# bldc_driver.net
KiCad netlist of a schematic drawn in EAGLE
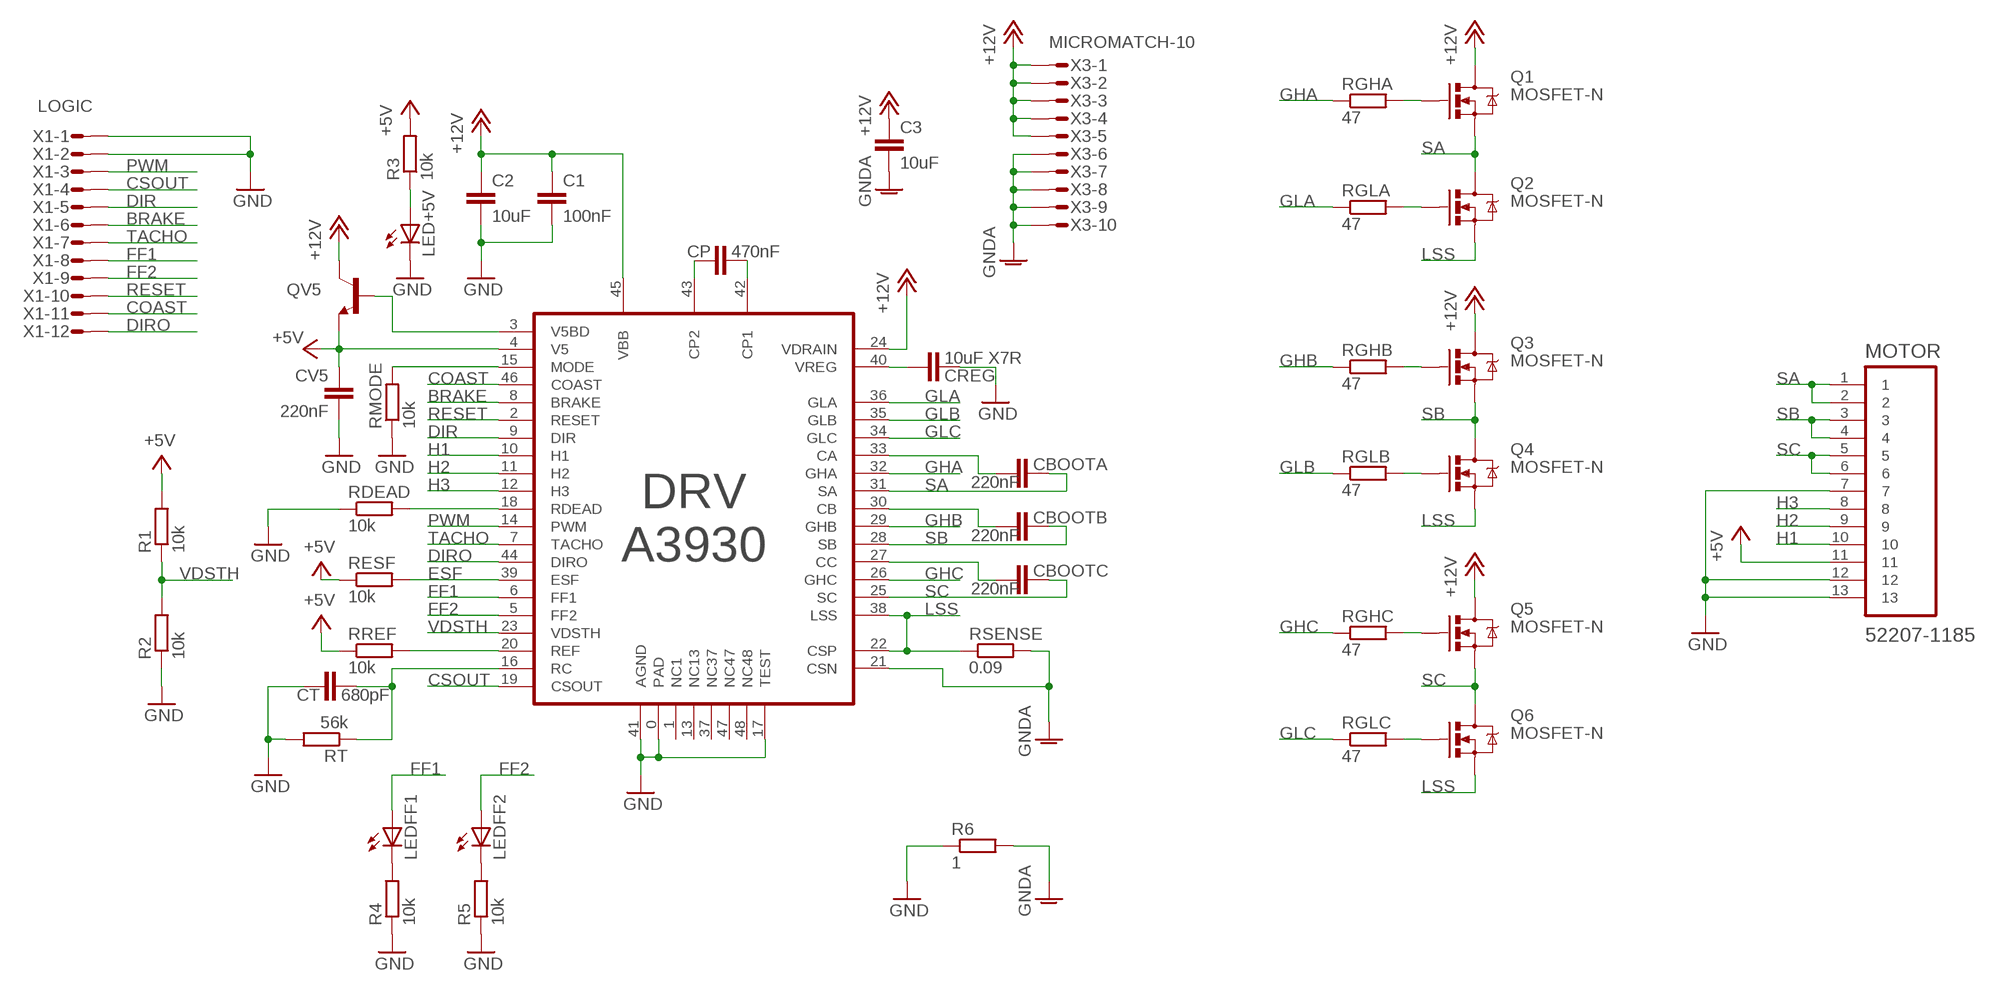
[diagram p0: schematic, sheet 1]

(export (version "E")
  (design (tool "Eeschema 10.0.6"))
  (components
    (comp (ref "C1")
      (value "100nF")
      (footprint "eagle-import:C0603")
      (libsource (lib "eagle-import") (part "C-EUC0603"))
    )
    (comp (ref "C2")
      (value "10uF")
      (footprint "eagle-import:C1206K")
      (libsource (lib "eagle-import") (part "C-EUC1206K"))
    )
    (comp (ref "C3")
      (value "10uF")
      (footprint "eagle-import:C1206K")
      (libsource (lib "eagle-import") (part "C-EUC1206K"))
    )
    (comp (ref "CBOOTA")
      (value "220nF")
      (footprint "eagle-import:C0603")
      (libsource (lib "eagle-import") (part "C-EUC0603"))
    )
    (comp (ref "CBOOTB")
      (value "220nF")
      (footprint "eagle-import:C0603")
      (libsource (lib "eagle-import") (part "C-EUC0603"))
    )
    (comp (ref "CBOOTC")
      (value "220nF")
      (footprint "eagle-import:C0603")
      (libsource (lib "eagle-import") (part "C-EUC0603"))
    )
    (comp (ref "CP")
      (value "470nF")
      (footprint "eagle-import:C0603")
      (libsource (lib "eagle-import") (part "C-EUC0603"))
    )
    (comp (ref "CREG")
      (value "10uF X7R")
      (footprint "eagle-import:C1206K")
      (libsource (lib "eagle-import") (part "C-EUC1206K"))
    )
    (comp (ref "CT")
      (value "680pF")
      (footprint "eagle-import:C0603")
      (libsource (lib "eagle-import") (part "C-EUC0603"))
    )
    (comp (ref "CV5")
      (value "220nF")
      (footprint "eagle-import:C0603")
      (libsource (lib "eagle-import") (part "C-EUC0603"))
    )
    (comp (ref "DRV")
      (value "A3930")
      (footprint "eagle-import:LQFP-48")
      (libsource (lib "eagle-import") (part "A3930"))
    )
    (comp (ref "LED+5V")
      (value "LEDCHIPLED_0603")
      (footprint "eagle-import:CHIPLED_0603")
      (libsource (lib "eagle-import") (part "LEDCHIPLED_0603"))
    )
    (comp (ref "LEDFF1")
      (value "LEDCHIPLED_0603")
      (footprint "eagle-import:CHIPLED_0603")
      (libsource (lib "eagle-import") (part "LEDCHIPLED_0603"))
    )
    (comp (ref "LEDFF2")
      (value "LEDCHIPLED_0603")
      (footprint "eagle-import:CHIPLED_0603")
      (libsource (lib "eagle-import") (part "LEDCHIPLED_0603"))
    )
    (comp (ref "MOTOR")
      (value "52207-1185")
      (footprint "eagle-import:MOLEX_52207-1185")
      (fields (field (name "MPN") "52207-1085"))
      (libsource (lib "eagle-import") (part "52207-1185"))
    )
    (comp (ref "Q1")
      (value "MOSFET-N")
      (footprint "eagle-import:SO08")
      (libsource (lib "eagle-import") (part "MOSFET-NCHANNELFDS6630A"))
    )
    (comp (ref "Q2")
      (value "MOSFET-N")
      (footprint "eagle-import:SO08")
      (libsource (lib "eagle-import") (part "MOSFET-NCHANNELFDS6630A"))
    )
    (comp (ref "Q3")
      (value "MOSFET-N")
      (footprint "eagle-import:SO08")
      (libsource (lib "eagle-import") (part "MOSFET-NCHANNELFDS6630A"))
    )
    (comp (ref "Q4")
      (value "MOSFET-N")
      (footprint "eagle-import:SO08")
      (libsource (lib "eagle-import") (part "MOSFET-NCHANNELFDS6630A"))
    )
    (comp (ref "Q5")
      (value "MOSFET-N")
      (footprint "eagle-import:SO08")
      (libsource (lib "eagle-import") (part "MOSFET-NCHANNELFDS6630A"))
    )
    (comp (ref "Q6")
      (value "MOSFET-N")
      (footprint "eagle-import:SO08")
      (libsource (lib "eagle-import") (part "MOSFET-NCHANNELFDS6630A"))
    )
    (comp (ref "QV5")
      (value "TRANSISTOR_NPNSOT23")
      (footprint "eagle-import:SOT23")
      (libsource (lib "eagle-import") (part "TRANSISTOR_NPNSOT23"))
    )
    (comp (ref "R1")
      (value "10k")
      (footprint "eagle-import:R0603")
      (libsource (lib "eagle-import") (part "R-EU_R0603"))
    )
    (comp (ref "R2")
      (value "10k")
      (footprint "eagle-import:R0603")
      (libsource (lib "eagle-import") (part "R-EU_R0603"))
    )
    (comp (ref "R3")
      (value "10k")
      (footprint "eagle-import:R0603")
      (libsource (lib "eagle-import") (part "R-EU_R0603"))
    )
    (comp (ref "R4")
      (value "10k")
      (footprint "eagle-import:R0603")
      (libsource (lib "eagle-import") (part "R-EU_R0603"))
    )
    (comp (ref "R5")
      (value "10k")
      (footprint "eagle-import:R0603")
      (libsource (lib "eagle-import") (part "R-EU_R0603"))
    )
    (comp (ref "R6")
      (value "1")
      (footprint "eagle-import:R0603")
      (libsource (lib "eagle-import") (part "R-EU_R0603"))
    )
    (comp (ref "RDEAD")
      (value "10k")
      (footprint "eagle-import:R0603")
      (libsource (lib "eagle-import") (part "R-EU_R0603"))
    )
    (comp (ref "RESF")
      (value "10k")
      (footprint "eagle-import:R0603")
      (libsource (lib "eagle-import") (part "R-EU_R0603"))
    )
    (comp (ref "RGHA")
      (value "47")
      (footprint "eagle-import:R0603")
      (libsource (lib "eagle-import") (part "R-EU_R0603"))
    )
    (comp (ref "RGHB")
      (value "47")
      (footprint "eagle-import:R0603")
      (libsource (lib "eagle-import") (part "R-EU_R0603"))
    )
    (comp (ref "RGHC")
      (value "47")
      (footprint "eagle-import:R0603")
      (libsource (lib "eagle-import") (part "R-EU_R0603"))
    )
    (comp (ref "RGLA")
      (value "47")
      (footprint "eagle-import:R0603")
      (libsource (lib "eagle-import") (part "R-EU_R0603"))
    )
    (comp (ref "RGLB")
      (value "47")
      (footprint "eagle-import:R0603")
      (libsource (lib "eagle-import") (part "R-EU_R0603"))
    )
    (comp (ref "RGLC")
      (value "47")
      (footprint "eagle-import:R0603")
      (libsource (lib "eagle-import") (part "R-EU_R0603"))
    )
    (comp (ref "RMODE")
      (value "10k")
      (footprint "eagle-import:R0603")
      (libsource (lib "eagle-import") (part "R-EU_R0603"))
    )
    (comp (ref "RREF")
      (value "10k")
      (footprint "eagle-import:R0603")
      (libsource (lib "eagle-import") (part "R-EU_R0603"))
    )
    (comp (ref "RSENSE")
      (value "0.09")
      (footprint "eagle-import:R2010")
      (libsource (lib "eagle-import") (part "R-EU_R2010"))
    )
    (comp (ref "RT")
      (value "56k")
      (footprint "eagle-import:R0603")
      (libsource (lib "eagle-import") (part "R-EU_R0603"))
    )
    (comp (ref "X1")
      (value "LOGIC")
      (footprint "eagle-import:MICROMATCH-12")
      (fields (field (name "MF") "FARNELL") (field (name "MPN") "8-215464-2"))
      (libsource (lib "eagle-import") (part "MICROMATCH-12"))
    )
    (comp (ref "X3")
      (value "MICROMATCH-10")
      (footprint "eagle-import:MICROMATCH-10")
      (fields (field (name "MF") "FARNELL") (field (name "MPN") "8-215464-0"))
      (libsource (lib "eagle-import") (part "MICROMATCH-10"))
    )
  )
  (nets
    (net (code "1") (name "+5V") (class "Default")
      (node (ref "CV5") (pin "2") (pinfunction "2_2") (pintype "passive"))
      (node (ref "DRV") (pin "4") (pinfunction "V5_4") (pintype "bidirectional"))
      (node (ref "MOTOR") (pin "11") (pinfunction "11_11") (pintype "passive"))
      (node (ref "QV5") (pin "2") (pinfunction "E_2") (pintype "passive"))
      (node (ref "R1") (pin "2") (pinfunction "2_2") (pintype "passive"))
      (node (ref "R3") (pin "2") (pinfunction "2_2") (pintype "passive"))
      (node (ref "RESF") (pin "1") (pinfunction "1_1") (pintype "passive"))
      (node (ref "RREF") (pin "1") (pinfunction "1_1") (pintype "passive"))
    )
    (net (code "2") (name "+12V") (class "Default")
      (node (ref "C1") (pin "1") (pinfunction "1_1") (pintype "passive"))
      (node (ref "C2") (pin "1") (pinfunction "1_1") (pintype "passive"))
      (node (ref "C3") (pin "1") (pinfunction "1_1") (pintype "passive"))
      (node (ref "DRV") (pin "24") (pinfunction "VDRAIN_24") (pintype "bidirectional"))
      (node (ref "DRV") (pin "45") (pinfunction "VBB_45") (pintype "bidirectional"))
      (node (ref "Q1") (pin "5") (pinfunction "D_5") (pintype "passive"))
      (node (ref "Q1") (pin "6") (pinfunction "D_6") (pintype "passive"))
      (node (ref "Q1") (pin "7") (pinfunction "D_7") (pintype "passive"))
      (node (ref "Q1") (pin "8") (pinfunction "D_8") (pintype "passive"))
      (node (ref "Q3") (pin "5") (pinfunction "D_5") (pintype "passive"))
      (node (ref "Q3") (pin "6") (pinfunction "D_6") (pintype "passive"))
      (node (ref "Q3") (pin "7") (pinfunction "D_7") (pintype "passive"))
      (node (ref "Q3") (pin "8") (pinfunction "D_8") (pintype "passive"))
      (node (ref "Q5") (pin "5") (pinfunction "D_5") (pintype "passive"))
      (node (ref "Q5") (pin "6") (pinfunction "D_6") (pintype "passive"))
      (node (ref "Q5") (pin "7") (pinfunction "D_7") (pintype "passive"))
      (node (ref "Q5") (pin "8") (pinfunction "D_8") (pintype "passive"))
      (node (ref "QV5") (pin "3") (pinfunction "C_3") (pintype "passive"))
      (node (ref "X3") (pin "1") (pinfunction "S_1") (pintype "passive"))
      (node (ref "X3") (pin "2") (pinfunction "S_2") (pintype "passive"))
      (node (ref "X3") (pin "3") (pinfunction "S_3") (pintype "passive"))
      (node (ref "X3") (pin "4") (pinfunction "S_4") (pintype "passive"))
      (node (ref "X3") (pin "5") (pinfunction "S_5") (pintype "passive"))
    )
    (net (code "3") (name "/BRAKE") (class "Default")
      (node (ref "DRV") (pin "8") (pinfunction "BRAKE_8") (pintype "bidirectional"))
      (node (ref "X1") (pin "6") (pinfunction "S_6") (pintype "passive"))
    )
    (net (code "4") (name "/COAST") (class "Default")
      (node (ref "DRV") (pin "46") (pinfunction "COAST_46") (pintype "bidirectional"))
      (node (ref "X1") (pin "11") (pinfunction "S_11") (pintype "passive"))
    )
    (net (code "5") (name "/CSOUT") (class "Default")
      (node (ref "DRV") (pin "19") (pinfunction "CSOUT_19") (pintype "bidirectional"))
      (node (ref "X1") (pin "4") (pinfunction "S_4") (pintype "passive"))
    )
    (net (code "6") (name "/DIR") (class "Default")
      (node (ref "DRV") (pin "9") (pinfunction "DIR_9") (pintype "bidirectional"))
      (node (ref "X1") (pin "5") (pinfunction "S_5") (pintype "passive"))
    )
    (net (code "7") (name "/DIRO") (class "Default")
      (node (ref "DRV") (pin "44") (pinfunction "DIRO_44") (pintype "bidirectional"))
      (node (ref "X1") (pin "12") (pinfunction "S_12") (pintype "passive"))
    )
    (net (code "8") (name "/ESF") (class "Default")
      (node (ref "DRV") (pin "39") (pinfunction "ESF_39") (pintype "bidirectional"))
      (node (ref "RESF") (pin "2") (pinfunction "2_2") (pintype "passive"))
    )
    (net (code "9") (name "/FF1") (class "Default")
      (node (ref "DRV") (pin "6") (pinfunction "FF1_6") (pintype "bidirectional"))
      (node (ref "LEDFF1") (pin "A") (pinfunction "A_A") (pintype "passive"))
      (node (ref "X1") (pin "8") (pinfunction "S_8") (pintype "passive"))
    )
    (net (code "10") (name "/FF2") (class "Default")
      (node (ref "DRV") (pin "5") (pinfunction "FF2_5") (pintype "bidirectional"))
      (node (ref "LEDFF2") (pin "A") (pinfunction "A_A") (pintype "passive"))
      (node (ref "X1") (pin "9") (pinfunction "S_9") (pintype "passive"))
    )
    (net (code "11") (name "/GHA") (class "Default")
      (node (ref "DRV") (pin "32") (pinfunction "GHA_32") (pintype "bidirectional"))
      (node (ref "RGHA") (pin "1") (pinfunction "1_1") (pintype "passive"))
    )
    (net (code "12") (name "/GHB") (class "Default")
      (node (ref "DRV") (pin "29") (pinfunction "GHB_29") (pintype "bidirectional"))
      (node (ref "RGHB") (pin "1") (pinfunction "1_1") (pintype "passive"))
    )
    (net (code "13") (name "/GHC") (class "Default")
      (node (ref "DRV") (pin "26") (pinfunction "GHC_26") (pintype "bidirectional"))
      (node (ref "RGHC") (pin "1") (pinfunction "1_1") (pintype "passive"))
    )
    (net (code "14") (name "/GLA") (class "Default")
      (node (ref "DRV") (pin "36") (pinfunction "GLA_36") (pintype "bidirectional"))
      (node (ref "RGLA") (pin "1") (pinfunction "1_1") (pintype "passive"))
    )
    (net (code "15") (name "/GLB") (class "Default")
      (node (ref "DRV") (pin "35") (pinfunction "GLB_35") (pintype "bidirectional"))
      (node (ref "RGLB") (pin "1") (pinfunction "1_1") (pintype "passive"))
    )
    (net (code "16") (name "/GLC") (class "Default")
      (node (ref "DRV") (pin "34") (pinfunction "GLC_34") (pintype "bidirectional"))
      (node (ref "RGLC") (pin "1") (pinfunction "1_1") (pintype "passive"))
    )
    (net (code "17") (name "/H1") (class "Default")
      (node (ref "DRV") (pin "10") (pinfunction "H1_10") (pintype "bidirectional"))
      (node (ref "MOTOR") (pin "10") (pinfunction "10_10") (pintype "passive"))
    )
    (net (code "18") (name "/H2") (class "Default")
      (node (ref "DRV") (pin "11") (pinfunction "H2_11") (pintype "bidirectional"))
      (node (ref "MOTOR") (pin "9") (pinfunction "9_9") (pintype "passive"))
    )
    (net (code "19") (name "/H3") (class "Default")
      (node (ref "DRV") (pin "12") (pinfunction "H3_12") (pintype "bidirectional"))
      (node (ref "MOTOR") (pin "8") (pinfunction "8_8") (pintype "passive"))
    )
    (net (code "20") (name "/LSS") (class "Default")
      (node (ref "DRV") (pin "22") (pinfunction "CSP_22") (pintype "bidirectional"))
      (node (ref "DRV") (pin "38") (pinfunction "LSS_38") (pintype "bidirectional"))
      (node (ref "Q2") (pin "1") (pinfunction "S_1") (pintype "passive"))
      (node (ref "Q2") (pin "2") (pinfunction "S_2") (pintype "passive"))
      (node (ref "Q2") (pin "3") (pinfunction "S_3") (pintype "passive"))
      (node (ref "Q4") (pin "1") (pinfunction "S_1") (pintype "passive"))
      (node (ref "Q4") (pin "2") (pinfunction "S_2") (pintype "passive"))
      (node (ref "Q4") (pin "3") (pinfunction "S_3") (pintype "passive"))
      (node (ref "Q6") (pin "1") (pinfunction "S_1") (pintype "passive"))
      (node (ref "Q6") (pin "2") (pinfunction "S_2") (pintype "passive"))
      (node (ref "Q6") (pin "3") (pinfunction "S_3") (pintype "passive"))
      (node (ref "RSENSE") (pin "1") (pinfunction "1_1") (pintype "passive"))
    )
    (net (code "21") (name "/PWM") (class "Default")
      (node (ref "DRV") (pin "14") (pinfunction "PWM_14") (pintype "bidirectional"))
      (node (ref "X1") (pin "3") (pinfunction "S_3") (pintype "passive"))
    )
    (net (code "22") (name "/RESET") (class "Default")
      (node (ref "DRV") (pin "2") (pinfunction "RESET_2") (pintype "bidirectional"))
      (node (ref "X1") (pin "10") (pinfunction "S_10") (pintype "passive"))
    )
    (net (code "23") (name "/SA") (class "Default")
      (node (ref "CBOOTA") (pin "2") (pinfunction "2_2") (pintype "passive"))
      (node (ref "DRV") (pin "31") (pinfunction "SA_31") (pintype "bidirectional"))
      (node (ref "MOTOR") (pin "1") (pinfunction "1_1") (pintype "passive"))
      (node (ref "MOTOR") (pin "2") (pinfunction "2_2") (pintype "passive"))
      (node (ref "Q1") (pin "1") (pinfunction "S_1") (pintype "passive"))
      (node (ref "Q1") (pin "2") (pinfunction "S_2") (pintype "passive"))
      (node (ref "Q1") (pin "3") (pinfunction "S_3") (pintype "passive"))
      (node (ref "Q2") (pin "5") (pinfunction "D_5") (pintype "passive"))
      (node (ref "Q2") (pin "6") (pinfunction "D_6") (pintype "passive"))
      (node (ref "Q2") (pin "7") (pinfunction "D_7") (pintype "passive"))
      (node (ref "Q2") (pin "8") (pinfunction "D_8") (pintype "passive"))
    )
    (net (code "24") (name "/SB") (class "Default")
      (node (ref "CBOOTB") (pin "2") (pinfunction "2_2") (pintype "passive"))
      (node (ref "DRV") (pin "28") (pinfunction "SB_28") (pintype "bidirectional"))
      (node (ref "MOTOR") (pin "3") (pinfunction "3_3") (pintype "passive"))
      (node (ref "MOTOR") (pin "4") (pinfunction "4_4") (pintype "passive"))
      (node (ref "Q3") (pin "1") (pinfunction "S_1") (pintype "passive"))
      (node (ref "Q3") (pin "2") (pinfunction "S_2") (pintype "passive"))
      (node (ref "Q3") (pin "3") (pinfunction "S_3") (pintype "passive"))
      (node (ref "Q4") (pin "5") (pinfunction "D_5") (pintype "passive"))
      (node (ref "Q4") (pin "6") (pinfunction "D_6") (pintype "passive"))
      (node (ref "Q4") (pin "7") (pinfunction "D_7") (pintype "passive"))
      (node (ref "Q4") (pin "8") (pinfunction "D_8") (pintype "passive"))
    )
    (net (code "25") (name "/SC") (class "Default")
      (node (ref "CBOOTC") (pin "2") (pinfunction "2_2") (pintype "passive"))
      (node (ref "DRV") (pin "25") (pinfunction "SC_25") (pintype "bidirectional"))
      (node (ref "MOTOR") (pin "5") (pinfunction "5_5") (pintype "passive"))
      (node (ref "MOTOR") (pin "6") (pinfunction "6_6") (pintype "passive"))
      (node (ref "Q5") (pin "1") (pinfunction "S_1") (pintype "passive"))
      (node (ref "Q5") (pin "2") (pinfunction "S_2") (pintype "passive"))
      (node (ref "Q5") (pin "3") (pinfunction "S_3") (pintype "passive"))
      (node (ref "Q6") (pin "5") (pinfunction "D_5") (pintype "passive"))
      (node (ref "Q6") (pin "6") (pinfunction "D_6") (pintype "passive"))
      (node (ref "Q6") (pin "7") (pinfunction "D_7") (pintype "passive"))
      (node (ref "Q6") (pin "8") (pinfunction "D_8") (pintype "passive"))
    )
    (net (code "26") (name "/TACHO") (class "Default")
      (node (ref "DRV") (pin "7") (pinfunction "TACHO_7") (pintype "bidirectional"))
      (node (ref "X1") (pin "7") (pinfunction "S_7") (pintype "passive"))
    )
    (net (code "27") (name "/VDSTH") (class "Default")
      (node (ref "DRV") (pin "23") (pinfunction "VDSTH_23") (pintype "bidirectional"))
      (node (ref "R1") (pin "1") (pinfunction "1_1") (pintype "passive"))
      (node (ref "R2") (pin "2") (pinfunction "2_2") (pintype "passive"))
    )
    (net (code "28") (name "GND") (class "Default")
      (node (ref "C1") (pin "2") (pinfunction "2_2") (pintype "passive"))
      (node (ref "C2") (pin "2") (pinfunction "2_2") (pintype "passive"))
      (node (ref "CREG") (pin "2") (pinfunction "2_2") (pintype "passive"))
      (node (ref "CT") (pin "2") (pinfunction "2_2") (pintype "passive"))
      (node (ref "CV5") (pin "1") (pinfunction "1_1") (pintype "passive"))
      (node (ref "DRV") (pin "0") (pinfunction "PAD_0") (pintype "bidirectional"))
      (node (ref "DRV") (pin "17") (pinfunction "TEST_17") (pintype "bidirectional"))
      (node (ref "DRV") (pin "41") (pinfunction "AGND_41") (pintype "bidirectional"))
      (node (ref "LED+5V") (pin "C") (pinfunction "C_C") (pintype "passive"))
      (node (ref "MOTOR") (pin "12") (pinfunction "12_12") (pintype "passive"))
      (node (ref "MOTOR") (pin "13") (pinfunction "13_13") (pintype "passive"))
      (node (ref "MOTOR") (pin "7") (pinfunction "7_7") (pintype "passive"))
      (node (ref "R2") (pin "1") (pinfunction "1_1") (pintype "passive"))
      (node (ref "R4") (pin "1") (pinfunction "1_1") (pintype "passive"))
      (node (ref "R5") (pin "1") (pinfunction "1_1") (pintype "passive"))
      (node (ref "R6") (pin "1") (pinfunction "1_1") (pintype "passive"))
      (node (ref "RDEAD") (pin "1") (pinfunction "1_1") (pintype "passive"))
      (node (ref "RMODE") (pin "1") (pinfunction "1_1") (pintype "passive"))
      (node (ref "RT") (pin "2") (pinfunction "2_2") (pintype "passive"))
      (node (ref "X1") (pin "1") (pinfunction "S_1") (pintype "passive"))
      (node (ref "X1") (pin "2") (pinfunction "S_2") (pintype "passive"))
    )
    (net (code "29") (name "GNDA") (class "Default")
      (node (ref "C3") (pin "2") (pinfunction "2_2") (pintype "passive"))
      (node (ref "DRV") (pin "21") (pinfunction "CSN_21") (pintype "bidirectional"))
      (node (ref "R6") (pin "2") (pinfunction "2_2") (pintype "passive"))
      (node (ref "RSENSE") (pin "2") (pinfunction "2_2") (pintype "passive"))
      (node (ref "X3") (pin "10") (pinfunction "S_10") (pintype "passive"))
      (node (ref "X3") (pin "6") (pinfunction "S_6") (pintype "passive"))
      (node (ref "X3") (pin "7") (pinfunction "S_7") (pintype "passive"))
      (node (ref "X3") (pin "8") (pinfunction "S_8") (pintype "passive"))
      (node (ref "X3") (pin "9") (pinfunction "S_9") (pintype "passive"))
    )
    (net (code "30") (name "Net-(DRV-CA)") (class "Default")
      (node (ref "CBOOTA") (pin "1") (pinfunction "1_1") (pintype "passive"))
      (node (ref "DRV") (pin "33") (pinfunction "CA_33") (pintype "bidirectional"))
    )
    (net (code "31") (name "Net-(DRV-CB)") (class "Default")
      (node (ref "CBOOTB") (pin "1") (pinfunction "1_1") (pintype "passive"))
      (node (ref "DRV") (pin "30") (pinfunction "CB_30") (pintype "bidirectional"))
    )
    (net (code "32") (name "Net-(DRV-CC)") (class "Default")
      (node (ref "CBOOTC") (pin "1") (pinfunction "1_1") (pintype "passive"))
      (node (ref "DRV") (pin "27") (pinfunction "CC_27") (pintype "bidirectional"))
    )
    (net (code "33") (name "Net-(DRV-CP1)") (class "Default")
      (node (ref "CP") (pin "1") (pinfunction "1_1") (pintype "passive"))
      (node (ref "DRV") (pin "42") (pinfunction "CP1_42") (pintype "bidirectional"))
    )
    (net (code "34") (name "Net-(DRV-CP2)") (class "Default")
      (node (ref "CP") (pin "2") (pinfunction "2_2") (pintype "passive"))
      (node (ref "DRV") (pin "43") (pinfunction "CP2_43") (pintype "bidirectional"))
    )
    (net (code "35") (name "Net-(DRV-MODE)") (class "Default")
      (node (ref "DRV") (pin "15") (pinfunction "MODE_15") (pintype "bidirectional"))
      (node (ref "RMODE") (pin "2") (pinfunction "2_2") (pintype "passive"))
    )
    (net (code "36") (name "Net-(DRV-RC)") (class "Default")
      (node (ref "CT") (pin "1") (pinfunction "1_1") (pintype "passive"))
      (node (ref "DRV") (pin "16") (pinfunction "RC_16") (pintype "bidirectional"))
      (node (ref "RT") (pin "1") (pinfunction "1_1") (pintype "passive"))
    )
    (net (code "37") (name "Net-(DRV-RDEAD)") (class "Default")
      (node (ref "DRV") (pin "18") (pinfunction "RDEAD_18") (pintype "bidirectional"))
      (node (ref "RDEAD") (pin "2") (pinfunction "2_2") (pintype "passive"))
    )
    (net (code "38") (name "Net-(DRV-REF)") (class "Default")
      (node (ref "DRV") (pin "20") (pinfunction "REF_20") (pintype "bidirectional"))
      (node (ref "RREF") (pin "2") (pinfunction "2_2") (pintype "passive"))
    )
    (net (code "39") (name "Net-(DRV-V5BD)") (class "Default")
      (node (ref "DRV") (pin "3") (pinfunction "V5BD_3") (pintype "bidirectional"))
      (node (ref "QV5") (pin "1") (pinfunction "B_1") (pintype "passive"))
    )
    (net (code "40") (name "Net-(DRV-VREG)") (class "Default")
      (node (ref "CREG") (pin "1") (pinfunction "1_1") (pintype "passive"))
      (node (ref "DRV") (pin "40") (pinfunction "VREG_40") (pintype "bidirectional"))
    )
    (net (code "41") (name "Net-(LED+5V-PadA)") (class "Default")
      (node (ref "LED+5V") (pin "A") (pinfunction "A_A") (pintype "passive"))
      (node (ref "R3") (pin "1") (pinfunction "1_1") (pintype "passive"))
    )
    (net (code "42") (name "Net-(LEDFF1-PadC)") (class "Default")
      (node (ref "LEDFF1") (pin "C") (pinfunction "C_C") (pintype "passive"))
      (node (ref "R4") (pin "2") (pinfunction "2_2") (pintype "passive"))
    )
    (net (code "43") (name "Net-(LEDFF2-PadC)") (class "Default")
      (node (ref "LEDFF2") (pin "C") (pinfunction "C_C") (pintype "passive"))
      (node (ref "R5") (pin "2") (pinfunction "2_2") (pintype "passive"))
    )
    (net (code "44") (name "Net-(Q1-G)") (class "Default")
      (node (ref "Q1") (pin "4") (pinfunction "G_4") (pintype "passive"))
      (node (ref "RGHA") (pin "2") (pinfunction "2_2") (pintype "passive"))
    )
    (net (code "45") (name "Net-(Q2-G)") (class "Default")
      (node (ref "Q2") (pin "4") (pinfunction "G_4") (pintype "passive"))
      (node (ref "RGLA") (pin "2") (pinfunction "2_2") (pintype "passive"))
    )
    (net (code "46") (name "Net-(Q3-G)") (class "Default")
      (node (ref "Q3") (pin "4") (pinfunction "G_4") (pintype "passive"))
      (node (ref "RGHB") (pin "2") (pinfunction "2_2") (pintype "passive"))
    )
    (net (code "47") (name "Net-(Q4-G)") (class "Default")
      (node (ref "Q4") (pin "4") (pinfunction "G_4") (pintype "passive"))
      (node (ref "RGLB") (pin "2") (pinfunction "2_2") (pintype "passive"))
    )
    (net (code "48") (name "Net-(Q5-G)") (class "Default")
      (node (ref "Q5") (pin "4") (pinfunction "G_4") (pintype "passive"))
      (node (ref "RGHC") (pin "2") (pinfunction "2_2") (pintype "passive"))
    )
    (net (code "49") (name "Net-(Q6-G)") (class "Default")
      (node (ref "Q6") (pin "4") (pinfunction "G_4") (pintype "passive"))
      (node (ref "RGLC") (pin "2") (pinfunction "2_2") (pintype "passive"))
    )
    (net (code "50") (name "unconnected-(DRV-NC1-Pad1)") (class "Default")
      (node (ref "DRV") (pin "1") (pinfunction "NC1_1") (pintype "no_connect"))
    )
    (net (code "51") (name "unconnected-(DRV-NC13-Pad13)") (class "Default")
      (node (ref "DRV") (pin "13") (pinfunction "NC13_13") (pintype "no_connect"))
    )
    (net (code "52") (name "unconnected-(DRV-NC37-Pad37)") (class "Default")
      (node (ref "DRV") (pin "37") (pinfunction "NC37_37") (pintype "no_connect"))
    )
    (net (code "53") (name "unconnected-(DRV-NC47-Pad47)") (class "Default")
      (node (ref "DRV") (pin "47") (pinfunction "NC47_47") (pintype "no_connect"))
    )
    (net (code "54") (name "unconnected-(DRV-NC48-Pad48)") (class "Default")
      (node (ref "DRV") (pin "48") (pinfunction "NC48_48") (pintype "no_connect"))
    )
  )
)
